# Wiring_Diagram.net
KiCad netlist of a schematic drawn in EAGLE
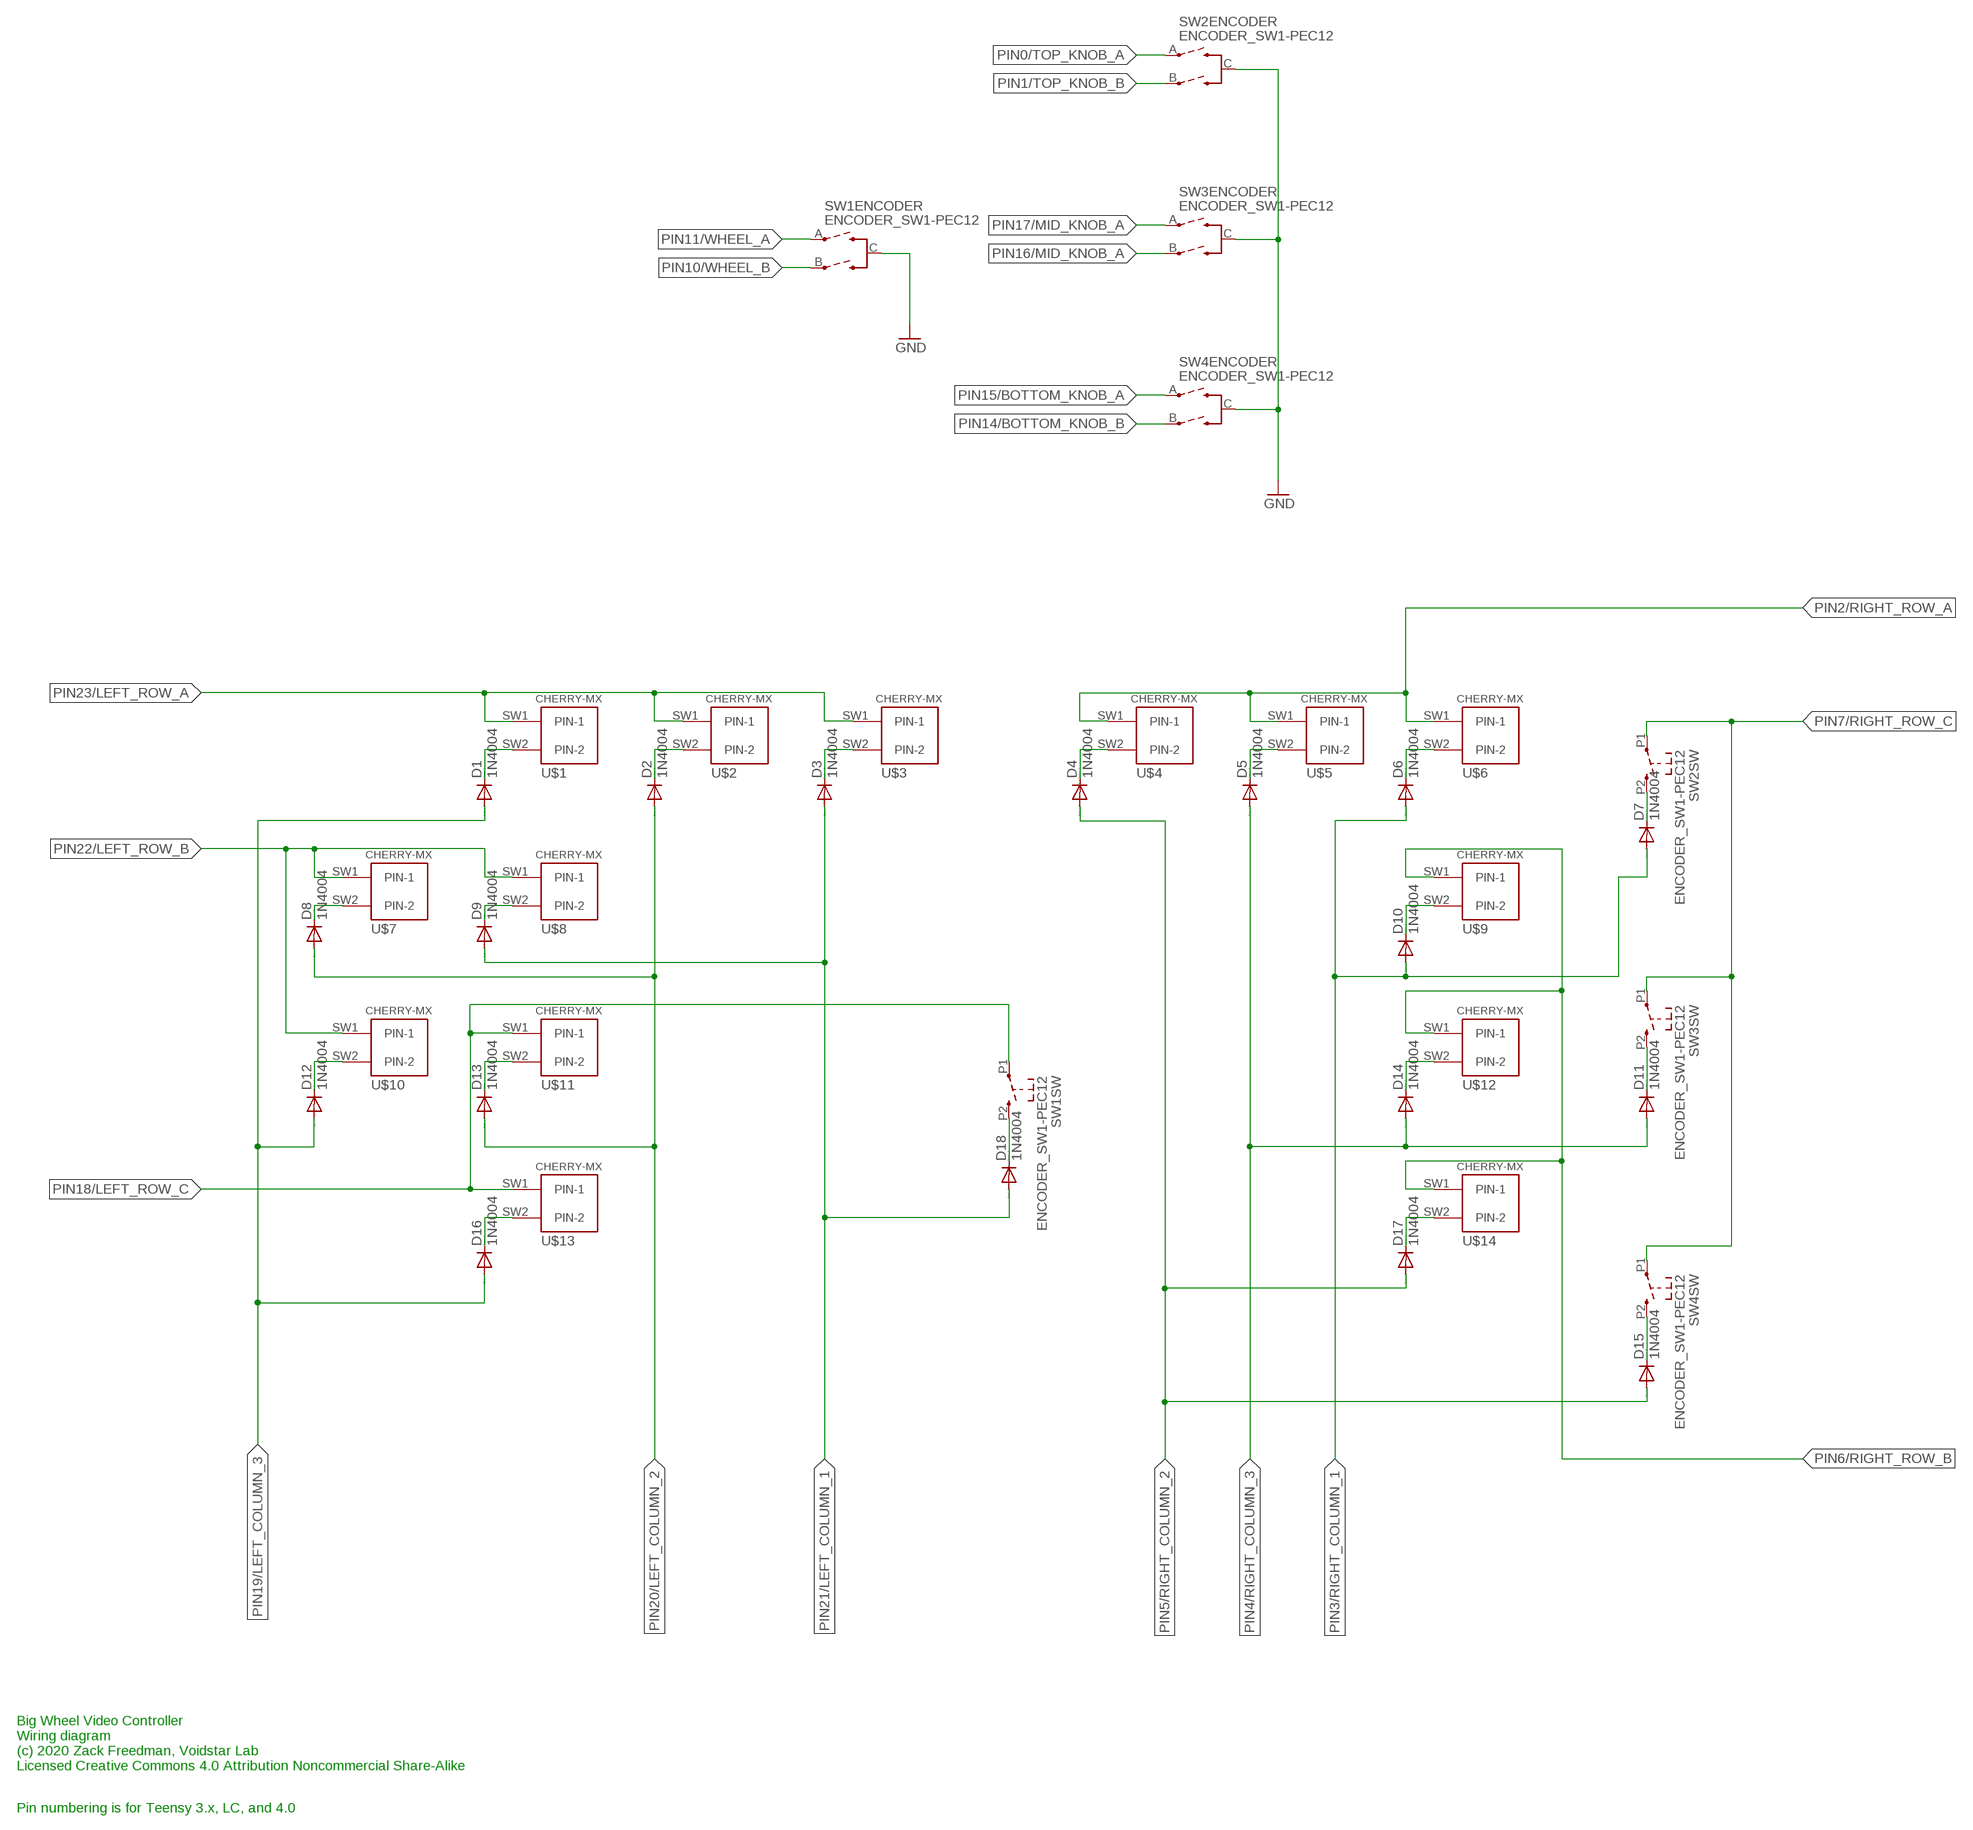
[diagram p0: schematic, sheet 1]

(export (version "E")
  (design (tool "Eeschema 10.0.6"))
  (components
    (comp (ref "D1")
      (value "1N4004")
      (footprint "eagle-import:DO41-10")
      (libsource (lib "eagle-import") (part "1N4004"))
    )
    (comp (ref "D2")
      (value "1N4004")
      (footprint "eagle-import:DO41-10")
      (libsource (lib "eagle-import") (part "1N4004"))
    )
    (comp (ref "D3")
      (value "1N4004")
      (footprint "eagle-import:DO41-10")
      (libsource (lib "eagle-import") (part "1N4004"))
    )
    (comp (ref "D4")
      (value "1N4004")
      (footprint "eagle-import:DO41-10")
      (libsource (lib "eagle-import") (part "1N4004"))
    )
    (comp (ref "D5")
      (value "1N4004")
      (footprint "eagle-import:DO41-10")
      (libsource (lib "eagle-import") (part "1N4004"))
    )
    (comp (ref "D6")
      (value "1N4004")
      (footprint "eagle-import:DO41-10")
      (libsource (lib "eagle-import") (part "1N4004"))
    )
    (comp (ref "D7")
      (value "1N4004")
      (footprint "eagle-import:DO41-10")
      (libsource (lib "eagle-import") (part "1N4004"))
    )
    (comp (ref "D8")
      (value "1N4004")
      (footprint "eagle-import:DO41-10")
      (libsource (lib "eagle-import") (part "1N4004"))
    )
    (comp (ref "D9")
      (value "1N4004")
      (footprint "eagle-import:DO41-10")
      (libsource (lib "eagle-import") (part "1N4004"))
    )
    (comp (ref "D10")
      (value "1N4004")
      (footprint "eagle-import:DO41-10")
      (libsource (lib "eagle-import") (part "1N4004"))
    )
    (comp (ref "D11")
      (value "1N4004")
      (footprint "eagle-import:DO41-10")
      (libsource (lib "eagle-import") (part "1N4004"))
    )
    (comp (ref "D12")
      (value "1N4004")
      (footprint "eagle-import:DO41-10")
      (libsource (lib "eagle-import") (part "1N4004"))
    )
    (comp (ref "D13")
      (value "1N4004")
      (footprint "eagle-import:DO41-10")
      (libsource (lib "eagle-import") (part "1N4004"))
    )
    (comp (ref "D14")
      (value "1N4004")
      (footprint "eagle-import:DO41-10")
      (libsource (lib "eagle-import") (part "1N4004"))
    )
    (comp (ref "D15")
      (value "1N4004")
      (footprint "eagle-import:DO41-10")
      (libsource (lib "eagle-import") (part "1N4004"))
    )
    (comp (ref "D16")
      (value "1N4004")
      (footprint "eagle-import:DO41-10")
      (libsource (lib "eagle-import") (part "1N4004"))
    )
    (comp (ref "D17")
      (value "1N4004")
      (footprint "eagle-import:DO41-10")
      (libsource (lib "eagle-import") (part "1N4004"))
    )
    (comp (ref "D18")
      (value "1N4004")
      (footprint "eagle-import:DO41-10")
      (libsource (lib "eagle-import") (part "1N4004"))
    )
    (comp (ref "SW1")
      (value "ENCODER_SW1-PEC12")
      (footprint "eagle-import:PEC12_INCREMENTAL_ENCODER")
      (libsource (lib "eagle-import") (part "ENCODER_SW1-PEC12"))
    )
    (comp (ref "SW2")
      (value "ENCODER_SW1-PEC12")
      (footprint "eagle-import:PEC12_INCREMENTAL_ENCODER")
      (libsource (lib "eagle-import") (part "ENCODER_SW1-PEC12"))
    )
    (comp (ref "SW3")
      (value "ENCODER_SW1-PEC12")
      (footprint "eagle-import:PEC12_INCREMENTAL_ENCODER")
      (libsource (lib "eagle-import") (part "ENCODER_SW1-PEC12"))
    )
    (comp (ref "SW4")
      (value "ENCODER_SW1-PEC12")
      (footprint "eagle-import:PEC12_INCREMENTAL_ENCODER")
      (libsource (lib "eagle-import") (part "ENCODER_SW1-PEC12"))
    )
    (comp (ref "U$1")
      (value "CHERRY-MX")
      (footprint "eagle-import:CHERRY-MX")
      (libsource (lib "eagle-import") (part "CHERRY-MX"))
    )
    (comp (ref "U$2")
      (value "CHERRY-MX")
      (footprint "eagle-import:CHERRY-MX")
      (libsource (lib "eagle-import") (part "CHERRY-MX"))
    )
    (comp (ref "U$3")
      (value "CHERRY-MX")
      (footprint "eagle-import:CHERRY-MX")
      (libsource (lib "eagle-import") (part "CHERRY-MX"))
    )
    (comp (ref "U$4")
      (value "CHERRY-MX")
      (footprint "eagle-import:CHERRY-MX")
      (libsource (lib "eagle-import") (part "CHERRY-MX"))
    )
    (comp (ref "U$5")
      (value "CHERRY-MX")
      (footprint "eagle-import:CHERRY-MX")
      (libsource (lib "eagle-import") (part "CHERRY-MX"))
    )
    (comp (ref "U$6")
      (value "CHERRY-MX")
      (footprint "eagle-import:CHERRY-MX")
      (libsource (lib "eagle-import") (part "CHERRY-MX"))
    )
    (comp (ref "U$7")
      (value "CHERRY-MX")
      (footprint "eagle-import:CHERRY-MX")
      (libsource (lib "eagle-import") (part "CHERRY-MX"))
    )
    (comp (ref "U$8")
      (value "CHERRY-MX")
      (footprint "eagle-import:CHERRY-MX")
      (libsource (lib "eagle-import") (part "CHERRY-MX"))
    )
    (comp (ref "U$9")
      (value "CHERRY-MX")
      (footprint "eagle-import:CHERRY-MX")
      (libsource (lib "eagle-import") (part "CHERRY-MX"))
    )
    (comp (ref "U$10")
      (value "CHERRY-MX")
      (footprint "eagle-import:CHERRY-MX")
      (libsource (lib "eagle-import") (part "CHERRY-MX"))
    )
    (comp (ref "U$11")
      (value "CHERRY-MX")
      (footprint "eagle-import:CHERRY-MX")
      (libsource (lib "eagle-import") (part "CHERRY-MX"))
    )
    (comp (ref "U$12")
      (value "CHERRY-MX")
      (footprint "eagle-import:CHERRY-MX")
      (libsource (lib "eagle-import") (part "CHERRY-MX"))
    )
    (comp (ref "U$13")
      (value "CHERRY-MX")
      (footprint "eagle-import:CHERRY-MX")
      (libsource (lib "eagle-import") (part "CHERRY-MX"))
    )
    (comp (ref "U$14")
      (value "CHERRY-MX")
      (footprint "eagle-import:CHERRY-MX")
      (libsource (lib "eagle-import") (part "CHERRY-MX"))
    )
  )
  (nets
    (net (code "1") (name "GND") (class "Default")
      (node (ref "SW1") (pin "C") (pinfunction "C_C") (pintype "passive"))
      (node (ref "SW2") (pin "C") (pinfunction "C_C") (pintype "passive"))
      (node (ref "SW3") (pin "C") (pinfunction "C_C") (pintype "passive"))
      (node (ref "SW4") (pin "C") (pinfunction "C_C") (pintype "passive"))
    )
    (net (code "2") (name "Net-(SW1B-2)") (class "Default")
      (node (ref "D18") (pin "C") (pinfunction "C_C") (pintype "passive"))
      (node (ref "SW1") (pin "P2") (pinfunction "2_P2") (pintype "passive"))
    )
    (net (code "3") (name "Net-(SW2B-2)") (class "Default")
      (node (ref "D7") (pin "C") (pinfunction "C_C") (pintype "passive"))
      (node (ref "SW2") (pin "P2") (pinfunction "2_P2") (pintype "passive"))
    )
    (net (code "4") (name "Net-(SW3B-2)") (class "Default")
      (node (ref "D11") (pin "C") (pinfunction "C_C") (pintype "passive"))
      (node (ref "SW3") (pin "P2") (pinfunction "2_P2") (pintype "passive"))
    )
    (net (code "5") (name "Net-(SW4B-2)") (class "Default")
      (node (ref "D15") (pin "C") (pinfunction "C_C") (pintype "passive"))
      (node (ref "SW4") (pin "P2") (pinfunction "2_P2") (pintype "passive"))
    )
    (net (code "6") (name "Net-(U$1-PIN-2)") (class "Default")
      (node (ref "D1") (pin "C") (pinfunction "C_C") (pintype "passive"))
      (node (ref "U$1") (pin "SW2") (pinfunction "PIN-2_SW2") (pintype "bidirectional"))
    )
    (net (code "7") (name "Net-(U$2-PIN-2)") (class "Default")
      (node (ref "D2") (pin "C") (pinfunction "C_C") (pintype "passive"))
      (node (ref "U$2") (pin "SW2") (pinfunction "PIN-2_SW2") (pintype "bidirectional"))
    )
    (net (code "8") (name "Net-(U$3-PIN-2)") (class "Default")
      (node (ref "D3") (pin "C") (pinfunction "C_C") (pintype "passive"))
      (node (ref "U$3") (pin "SW2") (pinfunction "PIN-2_SW2") (pintype "bidirectional"))
    )
    (net (code "9") (name "Net-(U$4-PIN-2)") (class "Default")
      (node (ref "D4") (pin "C") (pinfunction "C_C") (pintype "passive"))
      (node (ref "U$4") (pin "SW2") (pinfunction "PIN-2_SW2") (pintype "bidirectional"))
    )
    (net (code "10") (name "Net-(U$5-PIN-2)") (class "Default")
      (node (ref "D5") (pin "C") (pinfunction "C_C") (pintype "passive"))
      (node (ref "U$5") (pin "SW2") (pinfunction "PIN-2_SW2") (pintype "bidirectional"))
    )
    (net (code "11") (name "Net-(U$6-PIN-2)") (class "Default")
      (node (ref "D6") (pin "C") (pinfunction "C_C") (pintype "passive"))
      (node (ref "U$6") (pin "SW2") (pinfunction "PIN-2_SW2") (pintype "bidirectional"))
    )
    (net (code "12") (name "Net-(U$7-PIN-2)") (class "Default")
      (node (ref "D8") (pin "C") (pinfunction "C_C") (pintype "passive"))
      (node (ref "U$7") (pin "SW2") (pinfunction "PIN-2_SW2") (pintype "bidirectional"))
    )
    (net (code "13") (name "Net-(U$8-PIN-2)") (class "Default")
      (node (ref "D9") (pin "C") (pinfunction "C_C") (pintype "passive"))
      (node (ref "U$8") (pin "SW2") (pinfunction "PIN-2_SW2") (pintype "bidirectional"))
    )
    (net (code "14") (name "Net-(U$9-PIN-2)") (class "Default")
      (node (ref "D10") (pin "C") (pinfunction "C_C") (pintype "passive"))
      (node (ref "U$9") (pin "SW2") (pinfunction "PIN-2_SW2") (pintype "bidirectional"))
    )
    (net (code "15") (name "Net-(U$10-PIN-2)") (class "Default")
      (node (ref "D12") (pin "C") (pinfunction "C_C") (pintype "passive"))
      (node (ref "U$10") (pin "SW2") (pinfunction "PIN-2_SW2") (pintype "bidirectional"))
    )
    (net (code "16") (name "Net-(U$11-PIN-2)") (class "Default")
      (node (ref "D13") (pin "C") (pinfunction "C_C") (pintype "passive"))
      (node (ref "U$11") (pin "SW2") (pinfunction "PIN-2_SW2") (pintype "bidirectional"))
    )
    (net (code "17") (name "Net-(U$12-PIN-2)") (class "Default")
      (node (ref "D14") (pin "C") (pinfunction "C_C") (pintype "passive"))
      (node (ref "U$12") (pin "SW2") (pinfunction "PIN-2_SW2") (pintype "bidirectional"))
    )
    (net (code "18") (name "Net-(U$13-PIN-2)") (class "Default")
      (node (ref "D16") (pin "C") (pinfunction "C_C") (pintype "passive"))
      (node (ref "U$13") (pin "SW2") (pinfunction "PIN-2_SW2") (pintype "bidirectional"))
    )
    (net (code "19") (name "Net-(U$14-PIN-2)") (class "Default")
      (node (ref "D17") (pin "C") (pinfunction "C_C") (pintype "passive"))
      (node (ref "U$14") (pin "SW2") (pinfunction "PIN-2_SW2") (pintype "bidirectional"))
    )
    (net (code "20") (name "PIN0{slash}TOP_KNOB_A") (class "Default")
      (node (ref "SW2") (pin "A") (pinfunction "A_A") (pintype "passive"))
    )
    (net (code "21") (name "PIN1{slash}TOP_KNOB_B") (class "Default")
      (node (ref "SW2") (pin "B") (pinfunction "B_B") (pintype "passive"))
    )
    (net (code "22") (name "PIN2{slash}RIGHT_ROW_A") (class "Default")
      (node (ref "U$4") (pin "SW1") (pinfunction "PIN-1_SW1") (pintype "bidirectional"))
      (node (ref "U$5") (pin "SW1") (pinfunction "PIN-1_SW1") (pintype "bidirectional"))
      (node (ref "U$6") (pin "SW1") (pinfunction "PIN-1_SW1") (pintype "bidirectional"))
    )
    (net (code "23") (name "PIN3{slash}RIGHT_COLUMN_1") (class "Default")
      (node (ref "D10") (pin "A") (pinfunction "A_A") (pintype "passive"))
      (node (ref "D6") (pin "A") (pinfunction "A_A") (pintype "passive"))
      (node (ref "D7") (pin "A") (pinfunction "A_A") (pintype "passive"))
    )
    (net (code "24") (name "PIN4{slash}RIGHT_COLUMN_3") (class "Default")
      (node (ref "D11") (pin "A") (pinfunction "A_A") (pintype "passive"))
      (node (ref "D14") (pin "A") (pinfunction "A_A") (pintype "passive"))
      (node (ref "D5") (pin "A") (pinfunction "A_A") (pintype "passive"))
    )
    (net (code "25") (name "PIN5{slash}RIGHT_COLUMN_2") (class "Default")
      (node (ref "D15") (pin "A") (pinfunction "A_A") (pintype "passive"))
      (node (ref "D17") (pin "A") (pinfunction "A_A") (pintype "passive"))
      (node (ref "D4") (pin "A") (pinfunction "A_A") (pintype "passive"))
    )
    (net (code "26") (name "PIN6{slash}RIGHT_ROW_B") (class "Default")
      (node (ref "U$12") (pin "SW1") (pinfunction "PIN-1_SW1") (pintype "bidirectional"))
      (node (ref "U$14") (pin "SW1") (pinfunction "PIN-1_SW1") (pintype "bidirectional"))
      (node (ref "U$9") (pin "SW1") (pinfunction "PIN-1_SW1") (pintype "bidirectional"))
    )
    (net (code "27") (name "PIN7{slash}RIGHT_ROW_C") (class "Default")
      (node (ref "SW2") (pin "P1") (pinfunction "1_P1") (pintype "passive"))
      (node (ref "SW3") (pin "P1") (pinfunction "1_P1") (pintype "passive"))
      (node (ref "SW4") (pin "P1") (pinfunction "1_P1") (pintype "passive"))
    )
    (net (code "28") (name "PIN10{slash}WHEEL_B") (class "Default")
      (node (ref "SW1") (pin "B") (pinfunction "B_B") (pintype "passive"))
    )
    (net (code "29") (name "PIN11{slash}WHEEL_A") (class "Default")
      (node (ref "SW1") (pin "A") (pinfunction "A_A") (pintype "passive"))
    )
    (net (code "30") (name "PIN14{slash}BOTTOM_KNOB_B") (class "Default")
      (node (ref "SW4") (pin "B") (pinfunction "B_B") (pintype "passive"))
    )
    (net (code "31") (name "PIN15{slash}BOTTOM_KNOB_A") (class "Default")
      (node (ref "SW4") (pin "A") (pinfunction "A_A") (pintype "passive"))
    )
    (net (code "32") (name "PIN16{slash}MID_KNOB_A") (class "Default")
      (node (ref "SW3") (pin "B") (pinfunction "B_B") (pintype "passive"))
    )
    (net (code "33") (name "PIN17{slash}MID_KNOB_A") (class "Default")
      (node (ref "SW3") (pin "A") (pinfunction "A_A") (pintype "passive"))
    )
    (net (code "34") (name "PIN18{slash}LEFT_ROW_C") (class "Default")
      (node (ref "SW1") (pin "P1") (pinfunction "1_P1") (pintype "passive"))
      (node (ref "U$11") (pin "SW1") (pinfunction "PIN-1_SW1") (pintype "bidirectional"))
      (node (ref "U$13") (pin "SW1") (pinfunction "PIN-1_SW1") (pintype "bidirectional"))
    )
    (net (code "35") (name "PIN19{slash}LEFT_COLUMN_3") (class "Default")
      (node (ref "D1") (pin "A") (pinfunction "A_A") (pintype "passive"))
      (node (ref "D12") (pin "A") (pinfunction "A_A") (pintype "passive"))
      (node (ref "D16") (pin "A") (pinfunction "A_A") (pintype "passive"))
    )
    (net (code "36") (name "PIN20{slash}LEFT_COLUMN_2") (class "Default")
      (node (ref "D13") (pin "A") (pinfunction "A_A") (pintype "passive"))
      (node (ref "D2") (pin "A") (pinfunction "A_A") (pintype "passive"))
      (node (ref "D8") (pin "A") (pinfunction "A_A") (pintype "passive"))
    )
    (net (code "37") (name "PIN21{slash}LEFT_COLUMN_1") (class "Default")
      (node (ref "D18") (pin "A") (pinfunction "A_A") (pintype "passive"))
      (node (ref "D3") (pin "A") (pinfunction "A_A") (pintype "passive"))
      (node (ref "D9") (pin "A") (pinfunction "A_A") (pintype "passive"))
    )
    (net (code "38") (name "PIN22{slash}LEFT_ROW_B") (class "Default")
      (node (ref "U$10") (pin "SW1") (pinfunction "PIN-1_SW1") (pintype "bidirectional"))
      (node (ref "U$7") (pin "SW1") (pinfunction "PIN-1_SW1") (pintype "bidirectional"))
      (node (ref "U$8") (pin "SW1") (pinfunction "PIN-1_SW1") (pintype "bidirectional"))
    )
    (net (code "39") (name "PIN23{slash}LEFT_ROW_A") (class "Default")
      (node (ref "U$1") (pin "SW1") (pinfunction "PIN-1_SW1") (pintype "bidirectional"))
      (node (ref "U$2") (pin "SW1") (pinfunction "PIN-1_SW1") (pintype "bidirectional"))
      (node (ref "U$3") (pin "SW1") (pinfunction "PIN-1_SW1") (pintype "bidirectional"))
    )
  )
)
